# WeddingWidget.net
KiCad netlist of a schematic drawn in EAGLE
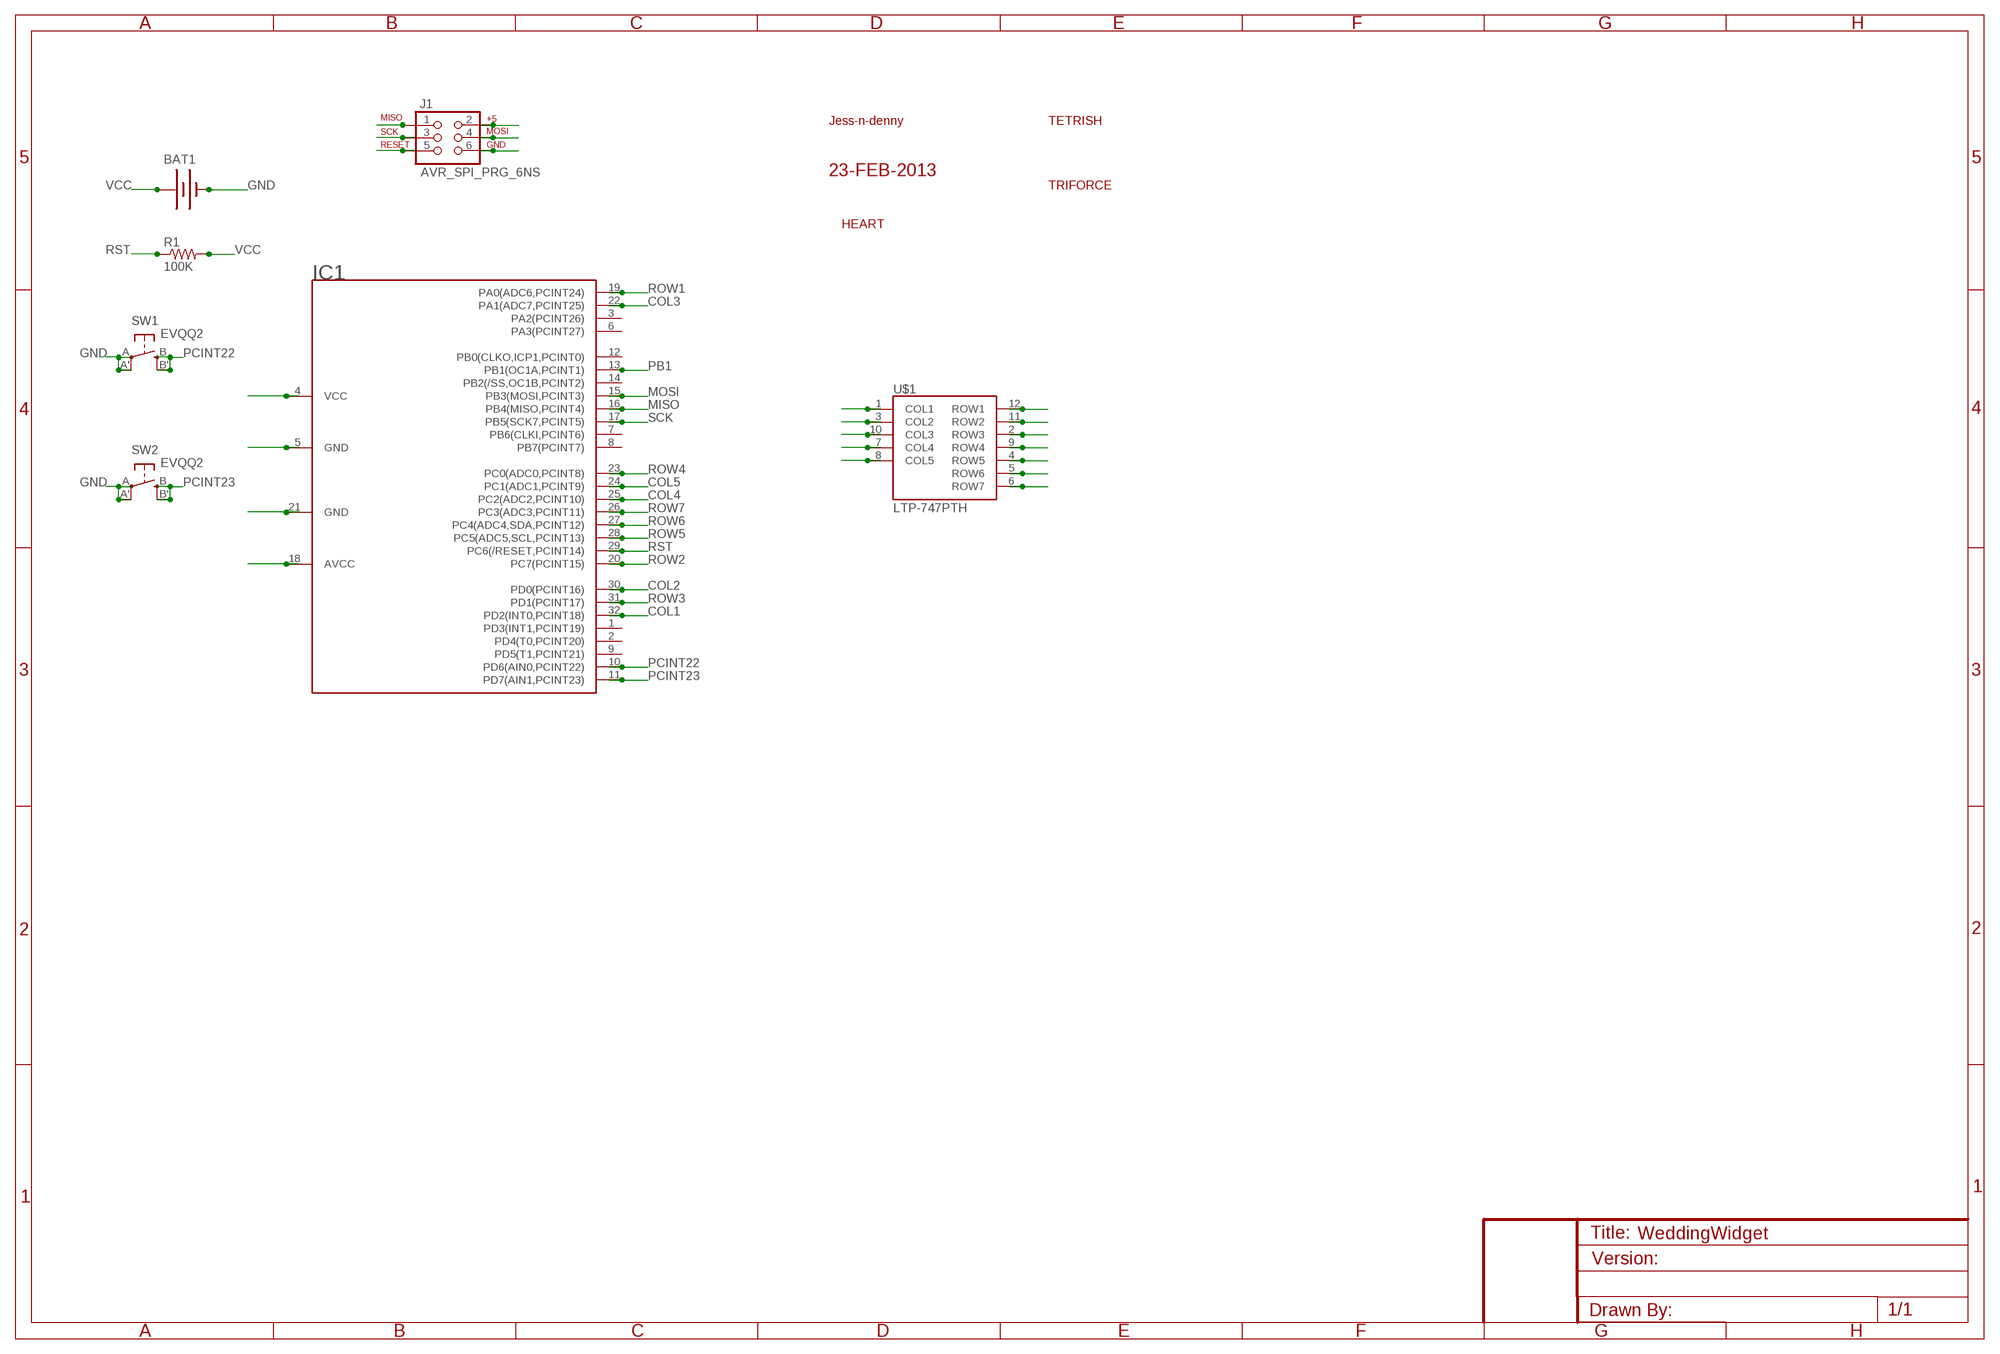
[diagram p0: schematic, sheet 1]

(export (version "E")
  (design (tool "Eeschema 10.0.6"))
  (components
    (comp (ref "BAT1")
      (value "BATTERY12MM")
      (footprint "eagle-import:BATTCON_12MM")
      (libsource (lib "eagle-import") (part "BATTERY12MM"))
    )
    (comp (ref "IC1")
      (value "ATTINY88")
      (footprint "eagle-import:TQFP32-08")
      (libsource (lib "eagle-import") (part "ATTINY88"))
    )
    (comp (ref "J1")
      (value "AVR_SPI_PRG_6NS")
      (footprint "eagle-import:2X3-NS")
      (libsource (lib "eagle-import") (part "AVR_SPI_PRG_6NS"))
    )
    (comp (ref "R1")
      (value "100K")
      (footprint "eagle-import:M0805")
      (libsource (lib "eagle-import") (part "R-US_M0805"))
    )
    (comp (ref "SW1")
      (value "EVQQ2")
      (footprint "eagle-import:EVQ-Q2")
      (libsource (lib "eagle-import") (part "EVQQ2"))
    )
    (comp (ref "SW2")
      (value "EVQQ2")
      (footprint "eagle-import:EVQ-Q2")
      (libsource (lib "eagle-import") (part "EVQQ2"))
    )
    (comp (ref "U$1")
      (value "LTP-747PTH")
      (footprint "eagle-import:LTP-747")
      (libsource (lib "eagle-import") (part "LTP-747PTH"))
    )
    (comp (ref "U$2")
      (value "JESS-N-DENNY")
      (footprint "eagle-import:JESS-N-DENNY")
      (libsource (lib "eagle-import") (part "JESS-N-DENNY"))
    )
    (comp (ref "U$3")
      (value "23FEB2013")
      (footprint "eagle-import:23FEB2013")
      (libsource (lib "eagle-import") (part "23FEB2013"))
    )
    (comp (ref "U$4")
      (value "HEART")
      (footprint "eagle-import:HEART")
      (libsource (lib "eagle-import") (part "HEART"))
    )
    (comp (ref "U$5")
      (value "TETRISH")
      (footprint "eagle-import:TETRISH")
      (libsource (lib "eagle-import") (part "TETRISH"))
    )
    (comp (ref "U$6")
      (value "TRIFORCE")
      (footprint "eagle-import:TRIFORCE")
      (libsource (lib "eagle-import") (part "TRIFORCE"))
    )
  )
  (nets
    (net (code "1") (name "/COL1") (class "Default")
      (node (ref "IC1") (pin "32") (pinfunction "PD2(INT0,PCINT18)_32") (pintype "bidirectional"))
      (node (ref "U$1") (pin "1") (pinfunction "COL1_1") (pintype "bidirectional"))
    )
    (net (code "2") (name "/COL2") (class "Default")
      (node (ref "IC1") (pin "30") (pinfunction "PD0(PCINT16)_30") (pintype "bidirectional"))
      (node (ref "U$1") (pin "3") (pinfunction "COL2_3") (pintype "bidirectional"))
    )
    (net (code "3") (name "/COL3") (class "Default")
      (node (ref "IC1") (pin "22") (pinfunction "PA1(ADC7,PCINT25)_22") (pintype "bidirectional"))
      (node (ref "U$1") (pin "10") (pinfunction "COL3_10") (pintype "bidirectional"))
    )
    (net (code "4") (name "/COL4") (class "Default")
      (node (ref "IC1") (pin "25") (pinfunction "PC2(ADC2,PCINT10)_25") (pintype "bidirectional"))
      (node (ref "U$1") (pin "7") (pinfunction "COL4_7") (pintype "bidirectional"))
    )
    (net (code "5") (name "/COL5") (class "Default")
      (node (ref "IC1") (pin "24") (pinfunction "PC1(ADC1,PCINT9)_24") (pintype "bidirectional"))
      (node (ref "U$1") (pin "8") (pinfunction "COL5_8") (pintype "bidirectional"))
    )
    (net (code "6") (name "/GND") (class "Default")
      (node (ref "BAT1") (pin "GND") (pinfunction "-_GND") (pintype "power_in"))
      (node (ref "IC1") (pin "21") (pinfunction "GND_21") (pintype "power_in"))
      (node (ref "IC1") (pin "5") (pinfunction "GND_5") (pintype "power_in"))
      (node (ref "J1") (pin "6") (pinfunction "6_6") (pintype "passive"))
      (node (ref "SW1") (pin "A") (pinfunction "P_A") (pintype "passive"))
      (node (ref "SW1") (pin "A'") (pinfunction "P1_A'") (pintype "passive"))
      (node (ref "SW2") (pin "A") (pinfunction "P_A") (pintype "passive"))
      (node (ref "SW2") (pin "A'") (pinfunction "P1_A'") (pintype "passive"))
    )
    (net (code "7") (name "/MISO") (class "Default")
      (node (ref "IC1") (pin "16") (pinfunction "PB4(MISO,PCINT4)_16") (pintype "bidirectional"))
      (node (ref "J1") (pin "1") (pinfunction "1_1") (pintype "passive"))
    )
    (net (code "8") (name "/MOSI") (class "Default")
      (node (ref "IC1") (pin "15") (pinfunction "PB3(MOSI,PCINT3)_15") (pintype "bidirectional"))
      (node (ref "J1") (pin "4") (pinfunction "4_4") (pintype "passive"))
    )
    (net (code "9") (name "/PB1") (class "Default")
      (node (ref "IC1") (pin "13") (pinfunction "PB1(OC1A,PCINT1)_13") (pintype "bidirectional"))
    )
    (net (code "10") (name "/PCINT22") (class "Default")
      (node (ref "IC1") (pin "10") (pinfunction "PD6(AIN0,PCINT22)_10") (pintype "bidirectional"))
      (node (ref "SW1") (pin "B") (pinfunction "S_B") (pintype "passive"))
      (node (ref "SW1") (pin "B'") (pinfunction "S1_B'") (pintype "passive"))
    )
    (net (code "11") (name "/PCINT23") (class "Default")
      (node (ref "IC1") (pin "11") (pinfunction "PD7(AIN1,PCINT23)_11") (pintype "bidirectional"))
      (node (ref "SW2") (pin "B") (pinfunction "S_B") (pintype "passive"))
      (node (ref "SW2") (pin "B'") (pinfunction "S1_B'") (pintype "passive"))
    )
    (net (code "12") (name "/ROW1") (class "Default")
      (node (ref "IC1") (pin "19") (pinfunction "PA0(ADC6,PCINT24)_19") (pintype "bidirectional"))
      (node (ref "U$1") (pin "12") (pinfunction "ROW1_12") (pintype "bidirectional"))
    )
    (net (code "13") (name "/ROW2") (class "Default")
      (node (ref "IC1") (pin "20") (pinfunction "PC7(PCINT15)_20") (pintype "bidirectional"))
      (node (ref "U$1") (pin "11") (pinfunction "ROW2_11") (pintype "bidirectional"))
    )
    (net (code "14") (name "/ROW3") (class "Default")
      (node (ref "IC1") (pin "31") (pinfunction "PD1(PCINT17)_31") (pintype "bidirectional"))
      (node (ref "U$1") (pin "2") (pinfunction "ROW3_2") (pintype "bidirectional"))
    )
    (net (code "15") (name "/ROW4") (class "Default")
      (node (ref "IC1") (pin "23") (pinfunction "PC0(ADC0,PCINT8)_23") (pintype "bidirectional"))
      (node (ref "U$1") (pin "9") (pinfunction "ROW4_9") (pintype "bidirectional"))
    )
    (net (code "16") (name "/ROW5") (class "Default")
      (node (ref "IC1") (pin "28") (pinfunction "PC5(ADC5,SCL,PCINT13)_28") (pintype "bidirectional"))
      (node (ref "U$1") (pin "4") (pinfunction "ROW5_4") (pintype "bidirectional"))
    )
    (net (code "17") (name "/ROW6") (class "Default")
      (node (ref "IC1") (pin "27") (pinfunction "PC4(ADC4,SDA,PCINT12)_27") (pintype "bidirectional"))
      (node (ref "U$1") (pin "5") (pinfunction "ROW6_5") (pintype "bidirectional"))
    )
    (net (code "18") (name "/ROW7") (class "Default")
      (node (ref "IC1") (pin "26") (pinfunction "PC3(ADC3,PCINT11)_26") (pintype "bidirectional"))
      (node (ref "U$1") (pin "6") (pinfunction "ROW7_6") (pintype "bidirectional"))
    )
    (net (code "19") (name "/RST") (class "Default")
      (node (ref "IC1") (pin "29") (pinfunction "PC6(/RESET,PCINT14)_29") (pintype "bidirectional"))
      (node (ref "J1") (pin "5") (pinfunction "5_5") (pintype "passive"))
      (node (ref "R1") (pin "1") (pinfunction "1_1") (pintype "passive"))
    )
    (net (code "20") (name "/SCK") (class "Default")
      (node (ref "IC1") (pin "17") (pinfunction "PB5(SCK7,PCINT5)_17") (pintype "bidirectional"))
      (node (ref "J1") (pin "3") (pinfunction "3_3") (pintype "passive"))
    )
    (net (code "21") (name "/VCC") (class "Default")
      (node (ref "BAT1") (pin "V+") (pinfunction "+_V+") (pintype "power_in"))
      (node (ref "IC1") (pin "18") (pinfunction "AVCC_18") (pintype "power_in"))
      (node (ref "IC1") (pin "4") (pinfunction "VCC_4") (pintype "power_in"))
      (node (ref "J1") (pin "2") (pinfunction "2_2") (pintype "passive"))
      (node (ref "R1") (pin "2") (pinfunction "2_2") (pintype "passive"))
    )
    (net (code "22") (name "unconnected-(IC1-PA2(PCINT26)-Pad3)") (class "Default")
      (node (ref "IC1") (pin "3") (pinfunction "PA2(PCINT26)_3") (pintype "bidirectional"))
    )
    (net (code "23") (name "unconnected-(IC1-PA3(PCINT27)-Pad6)") (class "Default")
      (node (ref "IC1") (pin "6") (pinfunction "PA3(PCINT27)_6") (pintype "bidirectional"))
    )
    (net (code "24") (name "unconnected-(IC1-PB0(CLKO,ICP1,PCINT0)-Pad12)") (class "Default")
      (node (ref "IC1") (pin "12") (pinfunction "PB0(CLKO,ICP1,PCINT0)_12") (pintype "bidirectional"))
    )
    (net (code "25") (name "unconnected-(IC1-PB2({slash}SS,OC1B,PCINT2)-Pad14)") (class "Default")
      (node (ref "IC1") (pin "14") (pinfunction "PB2(/SS,OC1B,PCINT2)_14") (pintype "bidirectional"))
    )
    (net (code "26") (name "unconnected-(IC1-PB6(CLKI,PCINT6)-Pad7)") (class "Default")
      (node (ref "IC1") (pin "7") (pinfunction "PB6(CLKI,PCINT6)_7") (pintype "bidirectional"))
    )
    (net (code "27") (name "unconnected-(IC1-PB7(PCINT7)-Pad8)") (class "Default")
      (node (ref "IC1") (pin "8") (pinfunction "PB7(PCINT7)_8") (pintype "bidirectional"))
    )
    (net (code "28") (name "unconnected-(IC1-PD3(INT1,PCINT19)-Pad1)") (class "Default")
      (node (ref "IC1") (pin "1") (pinfunction "PD3(INT1,PCINT19)_1") (pintype "bidirectional"))
    )
    (net (code "29") (name "unconnected-(IC1-PD4(T0,PCINT20)-Pad2)") (class "Default")
      (node (ref "IC1") (pin "2") (pinfunction "PD4(T0,PCINT20)_2") (pintype "bidirectional"))
    )
    (net (code "30") (name "unconnected-(IC1-PD5(T1,PCINT21)-Pad9)") (class "Default")
      (node (ref "IC1") (pin "9") (pinfunction "PD5(T1,PCINT21)_9") (pintype "bidirectional"))
    )
  )
)
